# cmoy-wide2.net
KiCad netlist of a schematic drawn in EAGLE
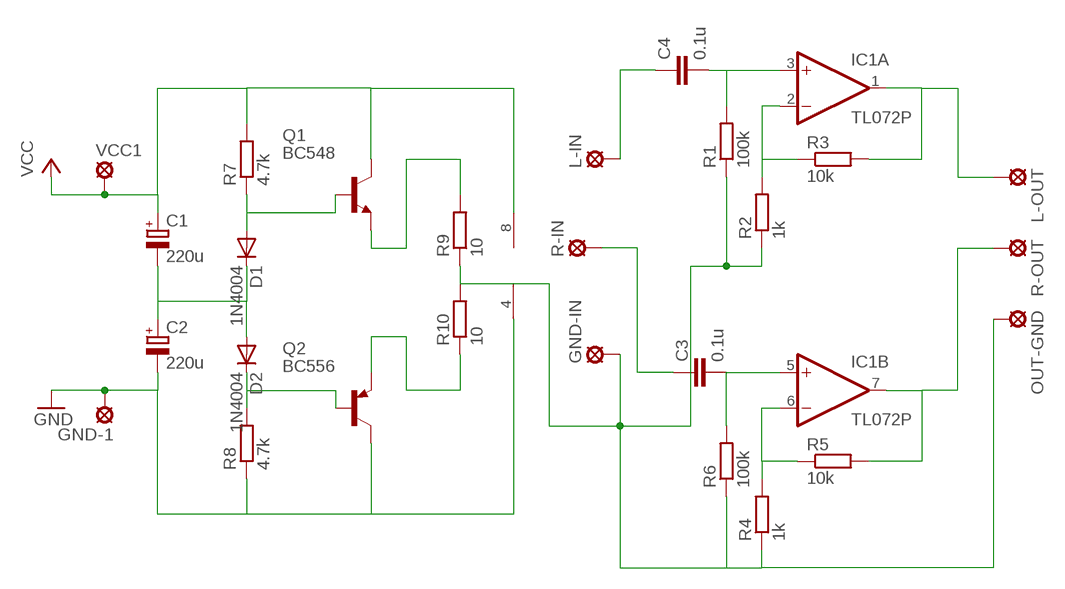
[diagram p0: schematic, sheet 1]

(export (version "E")
  (design (tool "Eeschema 10.0.6"))
  (components
    (comp (ref "C1")
      (value "220u")
      (footprint "eagle-import:E2,5-6")
      (libsource (lib "eagle-import") (part "CPOL-EUE2.5-6"))
    )
    (comp (ref "C2")
      (value "220u")
      (footprint "eagle-import:E2,5-6")
      (libsource (lib "eagle-import") (part "CPOL-EUE2.5-6"))
    )
    (comp (ref "C3")
      (value "0.1u")
      (footprint "eagle-import:C075-042X103")
      (libsource (lib "eagle-import") (part "C-EU075-042X103"))
    )
    (comp (ref "C4")
      (value "0.1u")
      (footprint "eagle-import:C075-042X103")
      (libsource (lib "eagle-import") (part "C-EU075-042X103"))
    )
    (comp (ref "D1")
      (value "1N4004")
      (footprint "eagle-import:DO41-10")
      (libsource (lib "eagle-import") (part "1N4004"))
    )
    (comp (ref "D2")
      (value "1N4004")
      (footprint "eagle-import:DO41-10")
      (libsource (lib "eagle-import") (part "1N4004"))
    )
    (comp (ref "GND-1")
      (value "LSP10")
      (footprint "eagle-import:LSP10")
      (libsource (lib "eagle-import") (part "LSP10"))
    )
    (comp (ref "GND-IN")
      (value "LSP10")
      (footprint "eagle-import:LSP10")
      (libsource (lib "eagle-import") (part "LSP10"))
    )
    (comp (ref "IC1")
      (value "TL072P")
      (footprint "eagle-import:DIL08")
      (libsource (lib "eagle-import") (part "TL072P"))
    )
    (comp (ref "L-IN")
      (value "LSP10")
      (footprint "eagle-import:LSP10")
      (libsource (lib "eagle-import") (part "LSP10"))
    )
    (comp (ref "L-OUT")
      (value "LSP10")
      (footprint "eagle-import:LSP10")
      (libsource (lib "eagle-import") (part "LSP10"))
    )
    (comp (ref "OUT-GND")
      (value "LSP10")
      (footprint "eagle-import:LSP10")
      (libsource (lib "eagle-import") (part "LSP10"))
    )
    (comp (ref "Q1")
      (value "BC548")
      (footprint "eagle-import:TO92-EBC")
      (libsource (lib "eagle-import") (part "BC548"))
    )
    (comp (ref "Q2")
      (value "BC556")
      (footprint "eagle-import:TO92-EBC")
      (libsource (lib "eagle-import") (part "BC556"))
    )
    (comp (ref "R-IN")
      (value "LSP10")
      (footprint "eagle-import:LSP10")
      (libsource (lib "eagle-import") (part "LSP10"))
    )
    (comp (ref "R-OUT")
      (value "LSP10")
      (footprint "eagle-import:LSP10")
      (libsource (lib "eagle-import") (part "LSP10"))
    )
    (comp (ref "R1")
      (value "100k")
      (footprint "eagle-import:0207_10")
      (libsource (lib "eagle-import") (part "R-EU_0207/10"))
    )
    (comp (ref "R2")
      (value "1k")
      (footprint "eagle-import:0207_10")
      (libsource (lib "eagle-import") (part "R-EU_0207/10"))
    )
    (comp (ref "R3")
      (value "10k")
      (footprint "eagle-import:0207_10")
      (libsource (lib "eagle-import") (part "R-EU_0207/10"))
    )
    (comp (ref "R4")
      (value "1k")
      (footprint "eagle-import:0207_10")
      (libsource (lib "eagle-import") (part "R-EU_0207/10"))
    )
    (comp (ref "R5")
      (value "10k")
      (footprint "eagle-import:0207_10")
      (libsource (lib "eagle-import") (part "R-EU_0207/10"))
    )
    (comp (ref "R6")
      (value "100k")
      (footprint "eagle-import:0207_10")
      (libsource (lib "eagle-import") (part "R-EU_0207/10"))
    )
    (comp (ref "R7")
      (value "4.7k")
      (footprint "eagle-import:0207_10")
      (libsource (lib "eagle-import") (part "R-EU_0207/10"))
    )
    (comp (ref "R8")
      (value "4.7k")
      (footprint "eagle-import:0207_10")
      (libsource (lib "eagle-import") (part "R-EU_0207/10"))
    )
    (comp (ref "R9")
      (value "10")
      (footprint "eagle-import:0207_10")
      (libsource (lib "eagle-import") (part "resistor_R-EU_0207/10"))
    )
    (comp (ref "R10")
      (value "10")
      (footprint "eagle-import:0207_10")
      (libsource (lib "eagle-import") (part "resistor_R-EU_0207/10"))
    )
    (comp (ref "VCC1")
      (value "LSP10")
      (footprint "eagle-import:LSP10")
      (libsource (lib "eagle-import") (part "LSP10"))
    )
  )
  (nets
    (net (code "1") (name "GND") (class "Default")
      (node (ref "C2") (pin "-") (pinfunction "-_-") (pintype "passive"))
      (node (ref "GND-1") (pin "MP") (pinfunction "MP_MP") (pintype "passive"))
      (node (ref "IC1") (pin "4") (pinfunction "V-_4") (pintype "power_in"))
      (node (ref "Q2") (pin "C") (pinfunction "C_C") (pintype "passive"))
      (node (ref "R8") (pin "1") (pinfunction "1_1") (pintype "passive"))
    )
    (net (code "2") (name "Net-(C1-Pad-)") (class "Default")
      (node (ref "C1") (pin "-") (pinfunction "-_-") (pintype "passive"))
      (node (ref "C2") (pin "+") (pinfunction "+_+") (pintype "passive"))
      (node (ref "D1") (pin "C") (pinfunction "C_C") (pintype "passive"))
      (node (ref "D2") (pin "A") (pinfunction "A_A") (pintype "passive"))
    )
    (net (code "3") (name "Net-(C3-Pad1)") (class "Default")
      (node (ref "C3") (pin "1") (pinfunction "1_1") (pintype "passive"))
      (node (ref "R-IN") (pin "MP") (pinfunction "MP_MP") (pintype "passive"))
    )
    (net (code "4") (name "Net-(C4-Pad1)") (class "Default")
      (node (ref "C4") (pin "1") (pinfunction "1_1") (pintype "passive"))
      (node (ref "L-IN") (pin "MP") (pinfunction "MP_MP") (pintype "passive"))
    )
    (net (code "5") (name "Net-(D1-PadA)") (class "Default")
      (node (ref "D1") (pin "A") (pinfunction "A_A") (pintype "passive"))
      (node (ref "Q1") (pin "B") (pinfunction "B_B") (pintype "passive"))
      (node (ref "R7") (pin "1") (pinfunction "1_1") (pintype "passive"))
    )
    (net (code "6") (name "Net-(D2-PadC)") (class "Default")
      (node (ref "D2") (pin "C") (pinfunction "C_C") (pintype "passive"))
      (node (ref "Q2") (pin "B") (pinfunction "B_B") (pintype "passive"))
      (node (ref "R8") (pin "2") (pinfunction "2_2") (pintype "passive"))
    )
    (net (code "7") (name "Net-(GND-IN-PadMP)") (class "Default")
      (node (ref "GND-IN") (pin "MP") (pinfunction "MP_MP") (pintype "passive"))
      (node (ref "OUT-GND") (pin "MP") (pinfunction "MP_MP") (pintype "passive"))
      (node (ref "R1") (pin "1") (pinfunction "1_1") (pintype "passive"))
      (node (ref "R10") (pin "2") (pinfunction "2_2") (pintype "passive"))
      (node (ref "R2") (pin "1") (pinfunction "1_1") (pintype "passive"))
      (node (ref "R4") (pin "1") (pinfunction "1_1") (pintype "passive"))
      (node (ref "R6") (pin "1") (pinfunction "1_1") (pintype "passive"))
      (node (ref "R9") (pin "1") (pinfunction "1_1") (pintype "passive"))
    )
    (net (code "8") (name "Net-(IC1A-+IN)") (class "Default")
      (node (ref "C4") (pin "2") (pinfunction "2_2") (pintype "passive"))
      (node (ref "IC1") (pin "3") (pinfunction "+IN_3") (pintype "input"))
      (node (ref "R1") (pin "2") (pinfunction "2_2") (pintype "passive"))
    )
    (net (code "9") (name "Net-(IC1A--IN)") (class "Default")
      (node (ref "IC1") (pin "2") (pinfunction "-IN_2") (pintype "input"))
      (node (ref "R2") (pin "2") (pinfunction "2_2") (pintype "passive"))
      (node (ref "R3") (pin "1") (pinfunction "1_1") (pintype "passive"))
    )
    (net (code "10") (name "Net-(IC1A-OUT)") (class "Default")
      (node (ref "IC1") (pin "1") (pinfunction "OUT_1") (pintype "output"))
      (node (ref "L-OUT") (pin "MP") (pinfunction "MP_MP") (pintype "passive"))
      (node (ref "R3") (pin "2") (pinfunction "2_2") (pintype "passive"))
    )
    (net (code "11") (name "Net-(IC1B-+IN)") (class "Default")
      (node (ref "C3") (pin "2") (pinfunction "2_2") (pintype "passive"))
      (node (ref "IC1") (pin "5") (pinfunction "+IN_5") (pintype "input"))
      (node (ref "R6") (pin "2") (pinfunction "2_2") (pintype "passive"))
    )
    (net (code "12") (name "Net-(IC1B--IN)") (class "Default")
      (node (ref "IC1") (pin "6") (pinfunction "-IN_6") (pintype "input"))
      (node (ref "R4") (pin "2") (pinfunction "2_2") (pintype "passive"))
      (node (ref "R5") (pin "1") (pinfunction "1_1") (pintype "passive"))
    )
    (net (code "13") (name "Net-(IC1B-OUT)") (class "Default")
      (node (ref "IC1") (pin "7") (pinfunction "OUT_7") (pintype "output"))
      (node (ref "R-OUT") (pin "MP") (pinfunction "MP_MP") (pintype "passive"))
      (node (ref "R5") (pin "2") (pinfunction "2_2") (pintype "passive"))
    )
    (net (code "14") (name "Net-(Q1-PadE)") (class "Default")
      (node (ref "Q1") (pin "E") (pinfunction "E_E") (pintype "passive"))
      (node (ref "R9") (pin "2") (pinfunction "2_2") (pintype "passive"))
    )
    (net (code "15") (name "Net-(Q2-PadE)") (class "Default")
      (node (ref "Q2") (pin "E") (pinfunction "E_E") (pintype "passive"))
      (node (ref "R10") (pin "1") (pinfunction "1_1") (pintype "passive"))
    )
    (net (code "16") (name "VCC") (class "Default")
      (node (ref "C1") (pin "+") (pinfunction "+_+") (pintype "passive"))
      (node (ref "IC1") (pin "8") (pinfunction "V+_8") (pintype "power_in"))
      (node (ref "Q1") (pin "C") (pinfunction "C_C") (pintype "passive"))
      (node (ref "R7") (pin "2") (pinfunction "2_2") (pintype "passive"))
      (node (ref "VCC1") (pin "MP") (pinfunction "MP_MP") (pintype "passive"))
    )
  )
)
